# benchBuddy.net
KiCad netlist of a schematic drawn in EAGLE
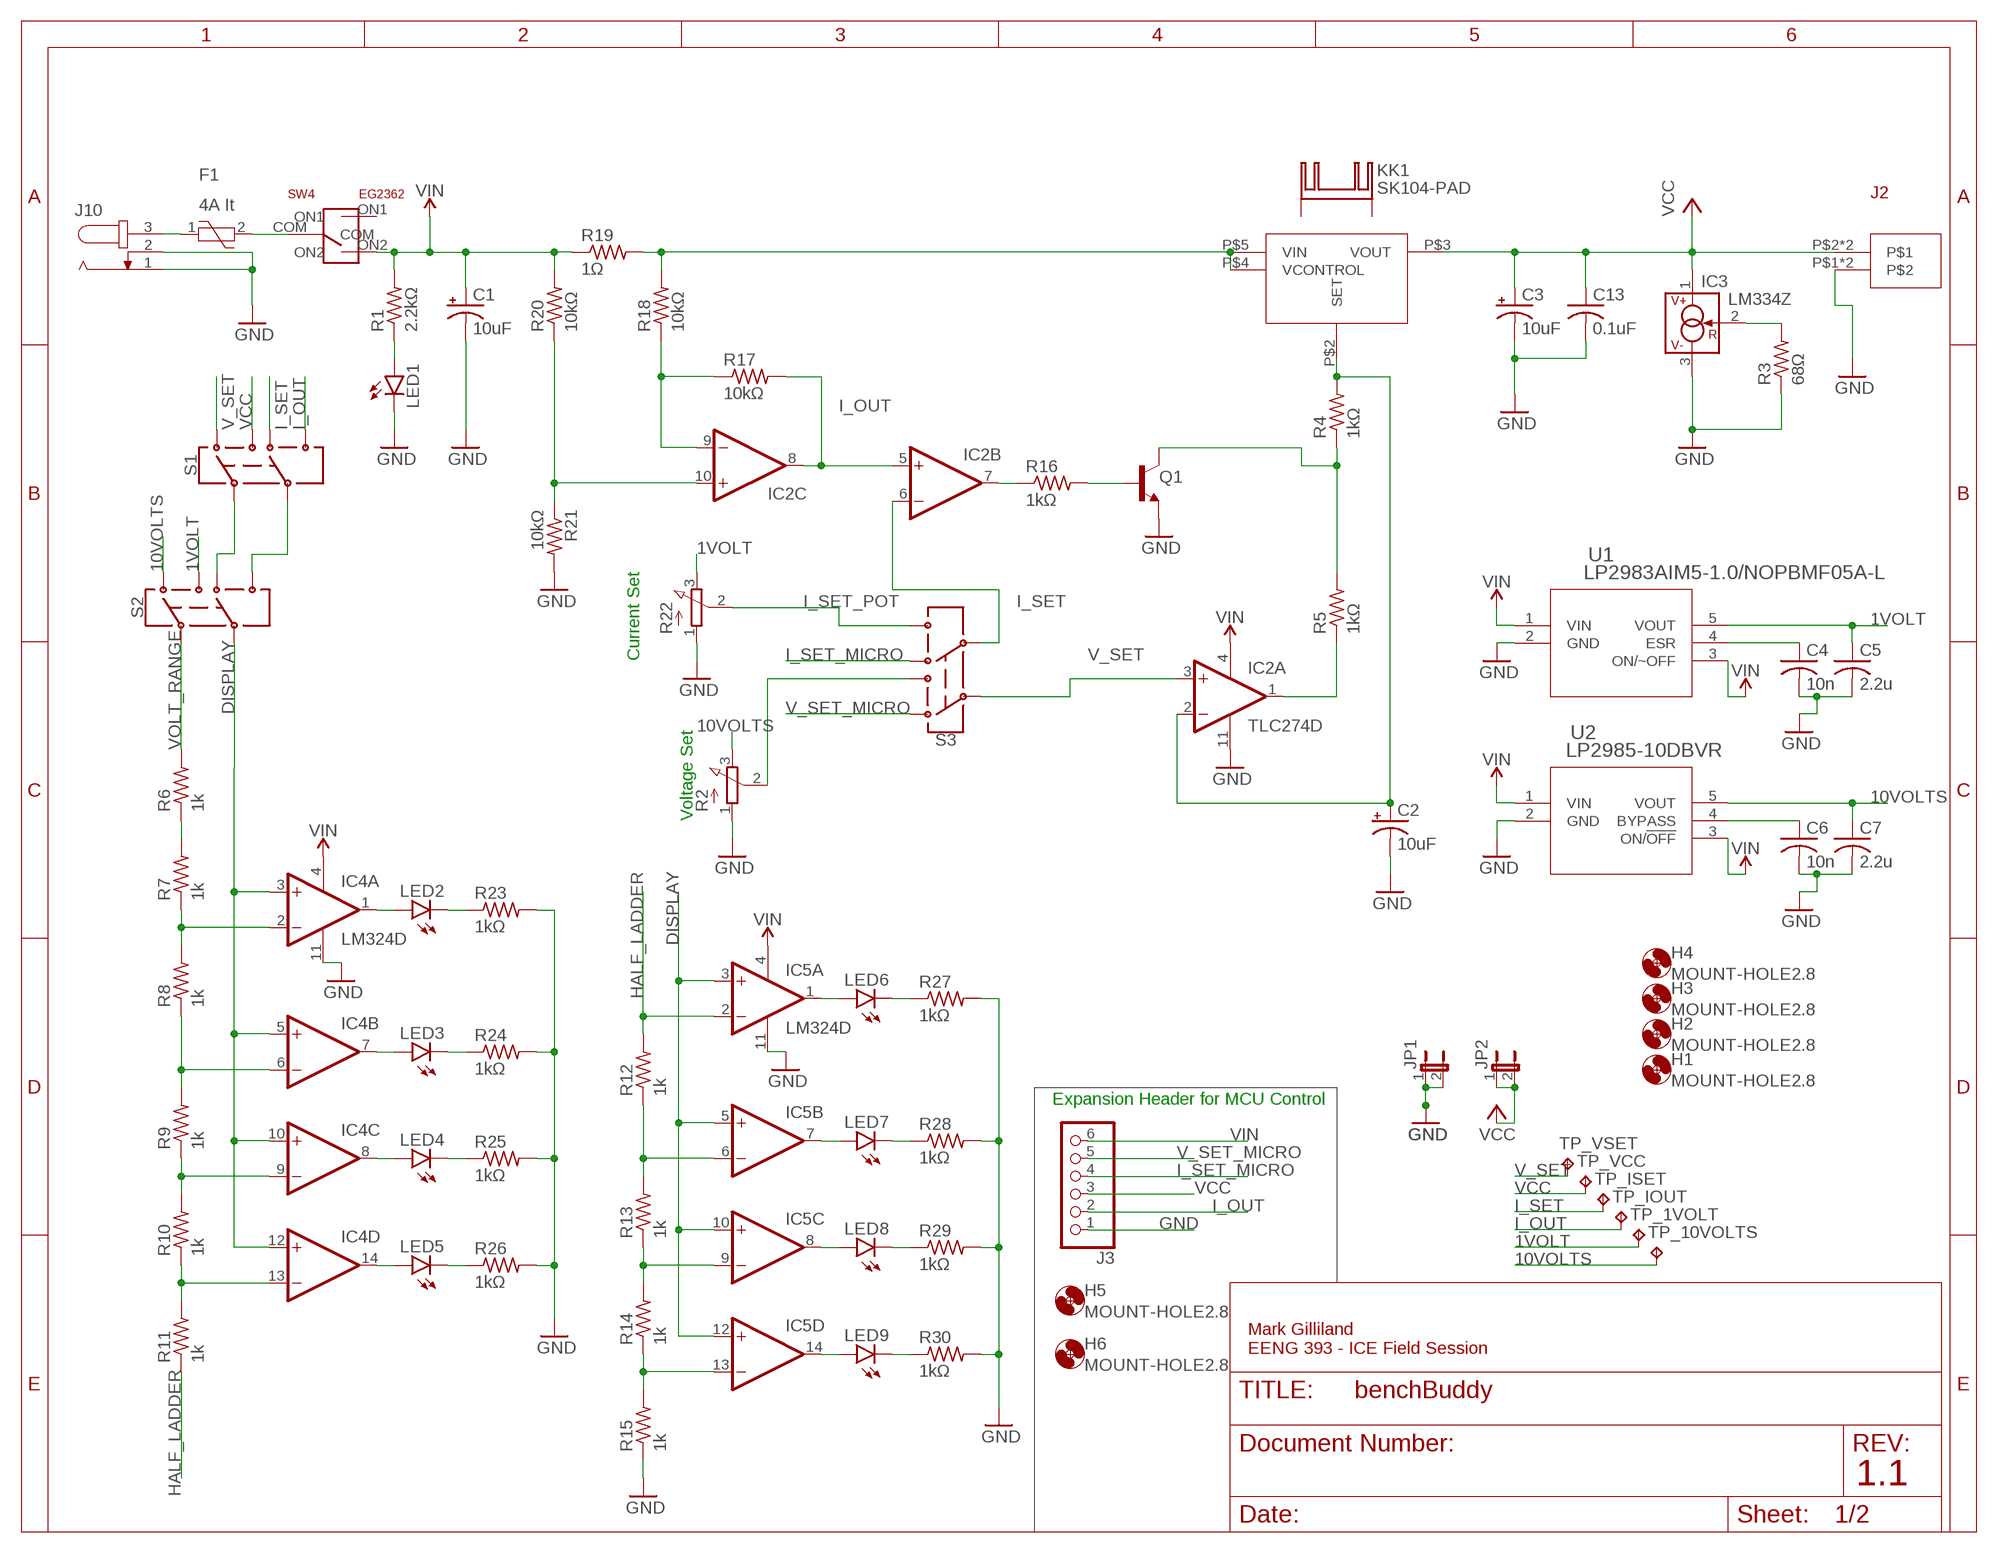
[diagram p0: schematic, sheet 1]
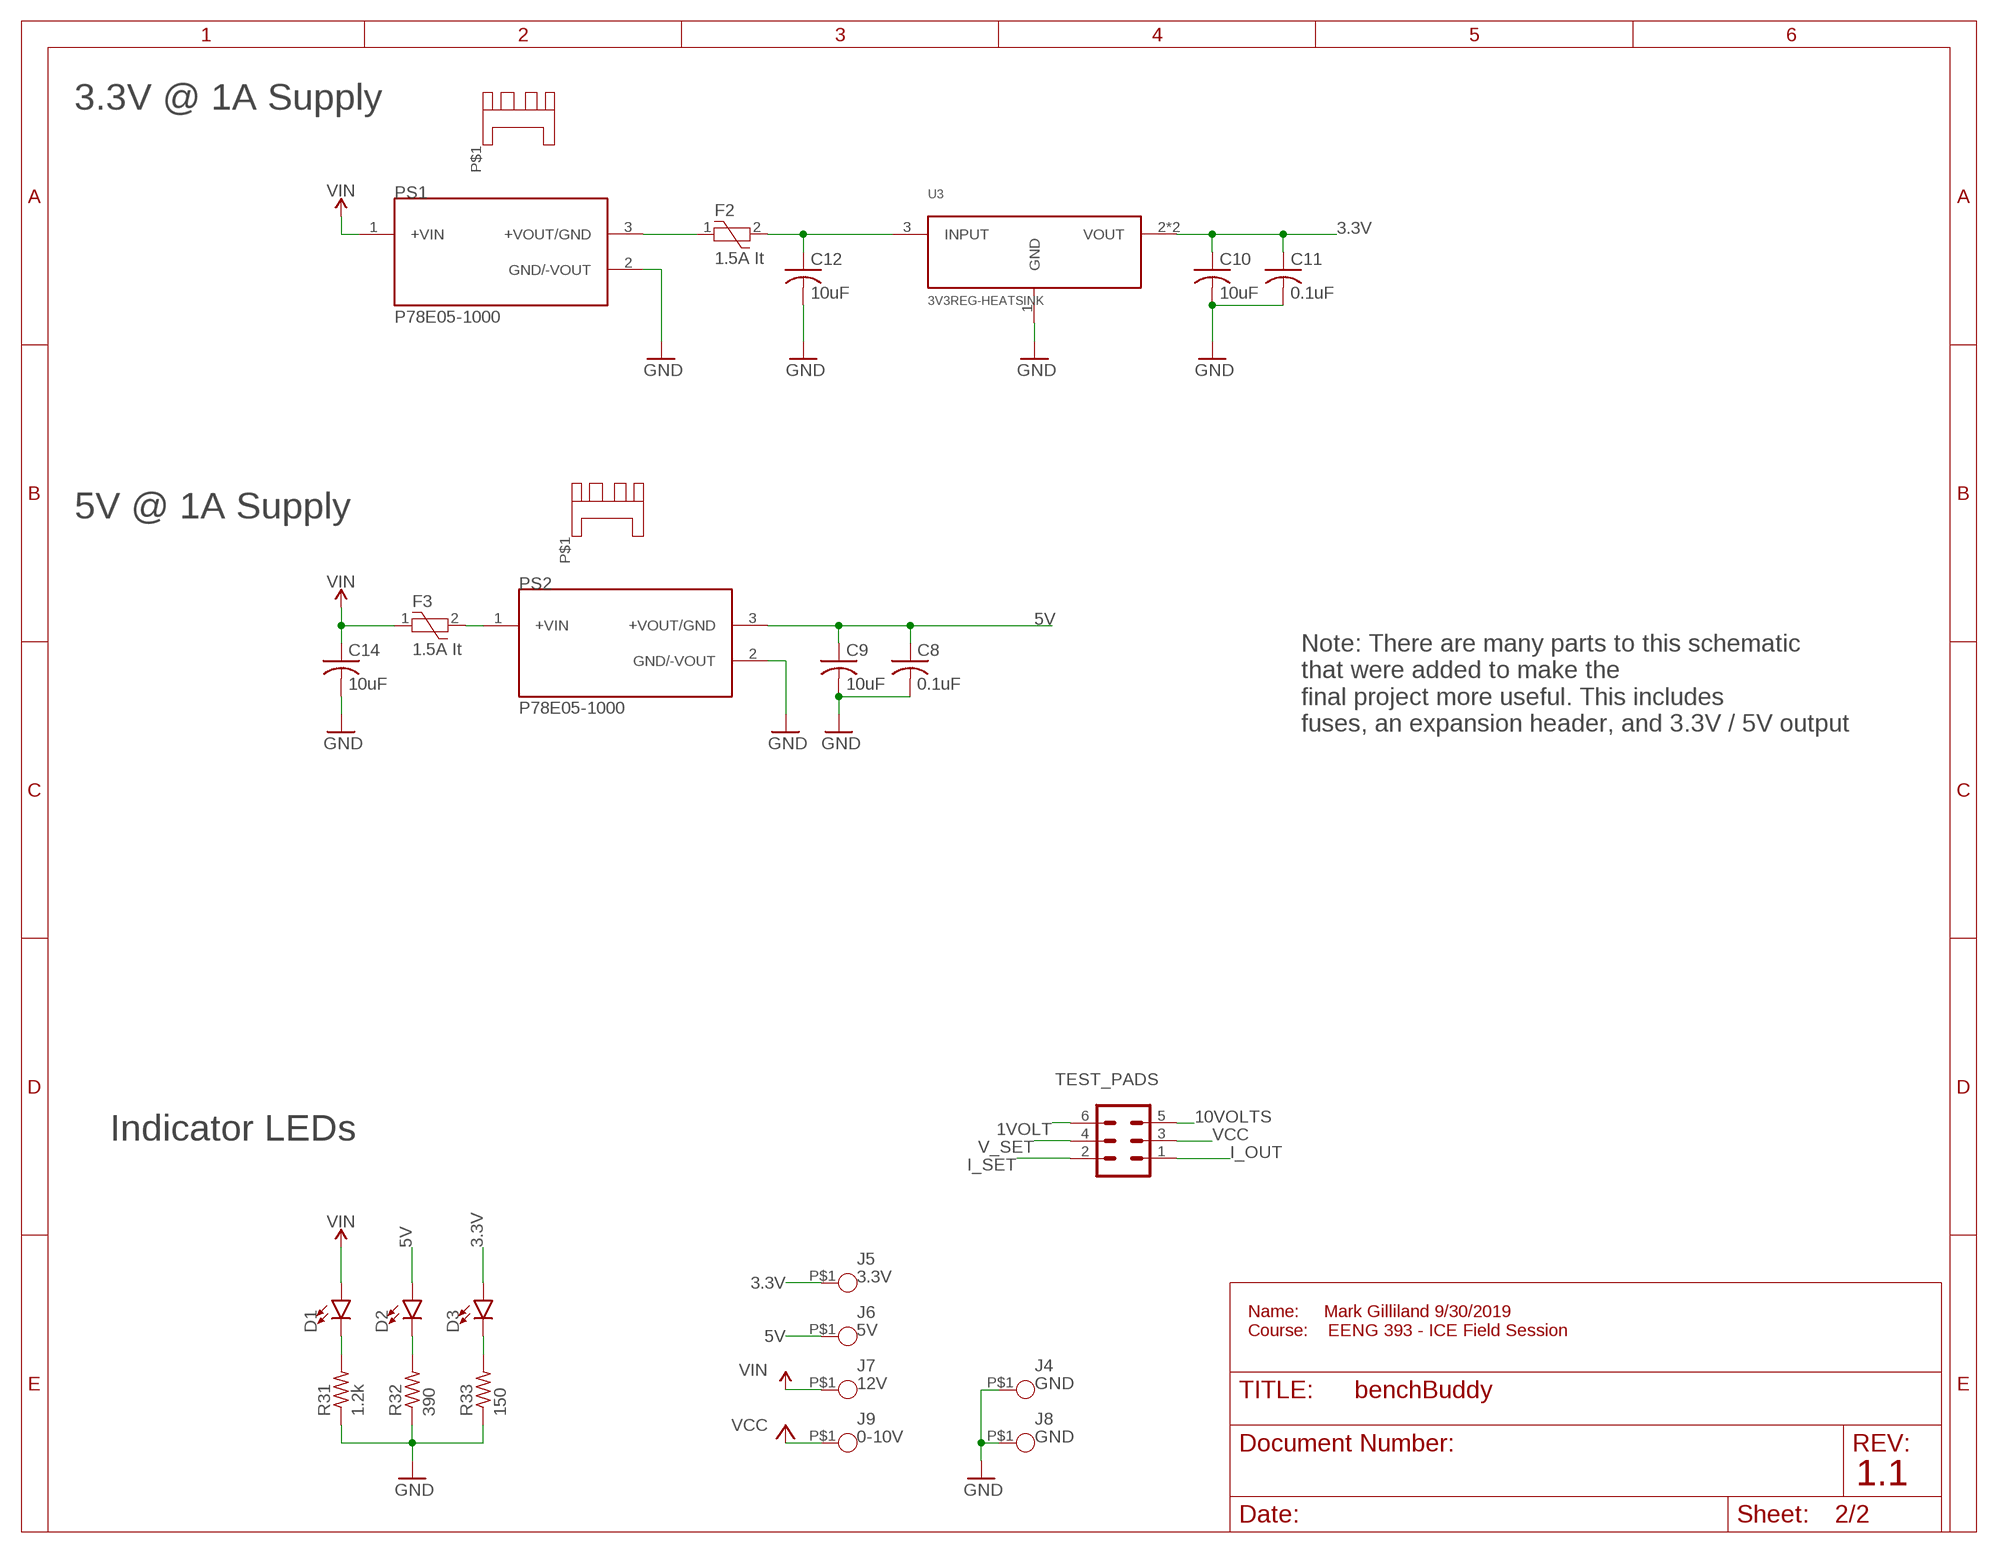
[diagram p1: schematic, sheet 2]

(export (version "E")
  (design (tool "Eeschema 10.0.6"))
  (components
    (comp (ref "C8")
      (value "0.1uF")
      (footprint "eagle-import:C0805")
      (libsource (lib "eagle-import") (part "C-USC0805"))
    )
    (comp (ref "C9")
      (value "10uF")
      (footprint "eagle-import:C0805")
      (libsource (lib "eagle-import") (part "C-USC0805"))
    )
    (comp (ref "C10")
      (value "10uF")
      (footprint "eagle-import:C0805")
      (libsource (lib "eagle-import") (part "C-USC0805"))
    )
    (comp (ref "C11")
      (value "0.1uF")
      (footprint "eagle-import:C0805")
      (libsource (lib "eagle-import") (part "C-USC0805"))
    )
    (comp (ref "C12")
      (value "10uF")
      (footprint "eagle-import:C0805")
      (libsource (lib "eagle-import") (part "C-USC0805"))
    )
    (comp (ref "C14")
      (value "10uF")
      (footprint "eagle-import:C0805")
      (libsource (lib "eagle-import") (part "C-USC0805"))
    )
    (comp (ref "D1")
      (value "LED3MM")
      (footprint "eagle-import:LED_3MM")
      (libsource (lib "eagle-import") (part "LED3MM"))
    )
    (comp (ref "D2")
      (value "LED3MM")
      (footprint "eagle-import:LED_3MM")
      (libsource (lib "eagle-import") (part "LED3MM"))
    )
    (comp (ref "D3")
      (value "LED3MM")
      (footprint "eagle-import:LED_3MM")
      (libsource (lib "eagle-import") (part "LED3MM"))
    )
    (comp (ref "F2")
      (value "1.5A It")
      (footprint "eagle-import:LITTELFUSE_MINISMDC260F_12-2")
      (libsource (lib "eagle-import") (part "FUSE"))
    )
    (comp (ref "F3")
      (value "1.5A It")
      (footprint "eagle-import:LITTELFUSE_MINISMDC260F_12-2")
      (libsource (lib "eagle-import") (part "FUSE"))
    )
    (comp (ref "J4")
      (value "GND")
      (footprint "eagle-import:FAT-PAD")
      (libsource (lib "eagle-import") (part "FAT-WIRE-TERM"))
    )
    (comp (ref "J5")
      (value "3.3V")
      (footprint "eagle-import:FAT-PAD")
      (libsource (lib "eagle-import") (part "FAT-WIRE-TERM"))
    )
    (comp (ref "J6")
      (value "5V")
      (footprint "eagle-import:FAT-PAD")
      (libsource (lib "eagle-import") (part "FAT-WIRE-TERM"))
    )
    (comp (ref "J7")
      (value "12V")
      (footprint "eagle-import:FAT-PAD")
      (libsource (lib "eagle-import") (part "FAT-WIRE-TERM"))
    )
    (comp (ref "J8")
      (value "GND")
      (footprint "eagle-import:FAT-PAD")
      (libsource (lib "eagle-import") (part "FAT-WIRE-TERM"))
    )
    (comp (ref "J9")
      (value "0-10V")
      (footprint "eagle-import:FAT-PAD")
      (libsource (lib "eagle-import") (part "FAT-WIRE-TERM"))
    )
    (comp (ref "PS1")
      (value "P78E05-1000")
      (footprint "eagle-import:CONV_P78E05-1000")
      (fields (field (name "MANUFACTURER") "CUI Inc"))
      (libsource (lib "eagle-import") (part "P78E05-1000"))
    )
    (comp (ref "PS2")
      (value "P78E05-1000")
      (footprint "eagle-import:CONV_P78E05-1000")
      (fields (field (name "MANUFACTURER") "CUI Inc"))
      (libsource (lib "eagle-import") (part "P78E05-1000"))
    )
    (comp (ref "R31")
      (value "1.2k")
      (footprint "eagle-import:R1206")
      (libsource (lib "eagle-import") (part "R-US_R1206"))
    )
    (comp (ref "R32")
      (value "390")
      (footprint "eagle-import:R1206")
      (libsource (lib "eagle-import") (part "R-US_R1206"))
    )
    (comp (ref "R33")
      (value "150")
      (footprint "eagle-import:R1206")
      (libsource (lib "eagle-import") (part "R-US_R1206"))
    )
    (comp (ref "TEST_PADS")
      (value "CONN_03X2NO_SILK")
      (footprint "eagle-import:2X3-NS")
      (libsource (lib "eagle-import") (part "CONN_03X2NO_SILK"))
    )
    (comp (ref "U$2")
      (value "HEATSINK_MINI")
      (footprint "eagle-import:HEATSINK_MINI")
      (libsource (lib "eagle-import") (part "HEATSINK_MINI"))
    )
    (comp (ref "U$3")
      (value "HEATSINK_MINI")
      (footprint "eagle-import:HEATSINK_MINI")
      (libsource (lib "eagle-import") (part "HEATSINK_MINI"))
    )
    (comp (ref "U3")
      (value "3V3REG-HEATSINK")
      (footprint "eagle-import:SOT223-HS")
      (libsource (lib "eagle-import") (part "3V3REG-HEATSINK"))
    )
    (comp (ref "C1")
      (value "10uF")
      (footprint "eagle-import:PANASONIC_B")
      (libsource (lib "eagle-import") (part "CPOL-USB"))
    )
    (comp (ref "C2")
      (value "10uF")
      (footprint "eagle-import:PANASONIC_B")
      (libsource (lib "eagle-import") (part "CPOL-USB"))
    )
    (comp (ref "C3")
      (value "10uF")
      (footprint "eagle-import:PANASONIC_B")
      (libsource (lib "eagle-import") (part "CPOL-USB"))
    )
    (comp (ref "C4")
      (value "10n")
      (footprint "eagle-import:C1206")
      (libsource (lib "eagle-import") (part "C-USC1206"))
    )
    (comp (ref "C5")
      (value "2.2u")
      (footprint "eagle-import:C1206")
      (libsource (lib "eagle-import") (part "C-USC1206"))
    )
    (comp (ref "C6")
      (value "10n")
      (footprint "eagle-import:C1206")
      (libsource (lib "eagle-import") (part "C-USC1206"))
    )
    (comp (ref "C7")
      (value "2.2u")
      (footprint "eagle-import:C1206")
      (libsource (lib "eagle-import") (part "C-USC1206"))
    )
    (comp (ref "C13")
      (value "0.1uF")
      (footprint "eagle-import:C0805")
      (libsource (lib "eagle-import") (part "C-USC0805"))
    )
    (comp (ref "F1")
      (value "4A It")
      (footprint "eagle-import:LITTELFUSE_MINISMDC260F_12-2")
      (libsource (lib "eagle-import") (part "FUSE"))
    )
    (comp (ref "H1")
      (value "MOUNT-HOLE2.8")
      (footprint "eagle-import:2,8")
      (libsource (lib "eagle-import") (part "MOUNT-HOLE2.8"))
    )
    (comp (ref "H2")
      (value "MOUNT-HOLE2.8")
      (footprint "eagle-import:2,8")
      (libsource (lib "eagle-import") (part "MOUNT-HOLE2.8"))
    )
    (comp (ref "H3")
      (value "MOUNT-HOLE2.8")
      (footprint "eagle-import:2,8")
      (libsource (lib "eagle-import") (part "MOUNT-HOLE2.8"))
    )
    (comp (ref "H4")
      (value "MOUNT-HOLE2.8")
      (footprint "eagle-import:2,8")
      (libsource (lib "eagle-import") (part "MOUNT-HOLE2.8"))
    )
    (comp (ref "H5")
      (value "MOUNT-HOLE2.8")
      (footprint "eagle-import:2,8")
      (libsource (lib "eagle-import") (part "MOUNT-HOLE2.8"))
    )
    (comp (ref "H6")
      (value "MOUNT-HOLE2.8")
      (footprint "eagle-import:2,8")
      (libsource (lib "eagle-import") (part "MOUNT-HOLE2.8"))
    )
    (comp (ref "IC2")
      (value "TLC274D")
      (footprint "eagle-import:SO14")
      (libsource (lib "eagle-import") (part "TLC274D"))
    )
    (comp (ref "IC3")
      (value "LM334Z")
      (footprint "eagle-import:TO92")
      (libsource (lib "eagle-import") (part "LM34Z3"))
    )
    (comp (ref "IC4")
      (value "LM324D")
      (footprint "eagle-import:SO14")
      (libsource (lib "eagle-import") (part "LM324D"))
    )
    (comp (ref "IC5")
      (value "LM324D")
      (footprint "eagle-import:SO14")
      (libsource (lib "eagle-import") (part "LM324D"))
    )
    (comp (ref "J2")
      (value "PHOENIX_SPRING_TERM_2POS")
      (footprint "eagle-import:SPRING_TERM_2POS")
      (libsource (lib "eagle-import") (part "PHOENIX_SPRING_TERM_2POS"))
    )
    (comp (ref "J3")
      (value "PINHD-1X6")
      (footprint "eagle-import:1X06")
      (libsource (lib "eagle-import") (part "PINHD-1X6"))
    )
    (comp (ref "J10")
      (value "JACK-PLUG0")
      (footprint "eagle-import:SPC4077")
      (libsource (lib "eagle-import") (part "JACK-PLUG0"))
    )
    (comp (ref "JP1")
      (value "JP1E")
      (footprint "eagle-import:JP1")
      (libsource (lib "eagle-import") (part "JP1E"))
    )
    (comp (ref "JP2")
      (value "JP1E")
      (footprint "eagle-import:JP1")
      (libsource (lib "eagle-import") (part "JP1E"))
    )
    (comp (ref "KK1")
      (value "SK104-PAD")
      (footprint "eagle-import:SK104-PAD")
      (libsource (lib "eagle-import") (part "SK104-PAD"))
    )
    (comp (ref "LED1")
      (value "LEDCHIPLED_1206")
      (footprint "eagle-import:CHIPLED_1206")
      (libsource (lib "eagle-import") (part "LEDCHIPLED_1206"))
    )
    (comp (ref "LED2")
      (value "LEDCHIPLED_1206")
      (footprint "eagle-import:CHIPLED_1206")
      (libsource (lib "eagle-import") (part "LEDCHIPLED_1206"))
    )
    (comp (ref "LED3")
      (value "LEDCHIPLED_1206")
      (footprint "eagle-import:CHIPLED_1206")
      (libsource (lib "eagle-import") (part "LEDCHIPLED_1206"))
    )
    (comp (ref "LED4")
      (value "LEDCHIPLED_1206")
      (footprint "eagle-import:CHIPLED_1206")
      (libsource (lib "eagle-import") (part "LEDCHIPLED_1206"))
    )
    (comp (ref "LED5")
      (value "LEDCHIPLED_1206")
      (footprint "eagle-import:CHIPLED_1206")
      (libsource (lib "eagle-import") (part "LEDCHIPLED_1206"))
    )
    (comp (ref "LED6")
      (value "LEDCHIPLED_1206")
      (footprint "eagle-import:CHIPLED_1206")
      (libsource (lib "eagle-import") (part "LEDCHIPLED_1206"))
    )
    (comp (ref "LED7")
      (value "LEDCHIPLED_1206")
      (footprint "eagle-import:CHIPLED_1206")
      (libsource (lib "eagle-import") (part "LEDCHIPLED_1206"))
    )
    (comp (ref "LED8")
      (value "LEDCHIPLED_1206")
      (footprint "eagle-import:CHIPLED_1206")
      (libsource (lib "eagle-import") (part "LEDCHIPLED_1206"))
    )
    (comp (ref "LED9")
      (value "LEDCHIPLED_1206")
      (footprint "eagle-import:CHIPLED_1206")
      (libsource (lib "eagle-import") (part "LEDCHIPLED_1206"))
    )
    (comp (ref "Q1")
      (value "600mA/40V")
      (footprint "eagle-import:SOT23-3")
      (libsource (lib "eagle-import") (part "TRANS_NPN-MMBT2222AL"))
    )
    (comp (ref "R1")
      (value "2.2kΩ")
      (footprint "eagle-import:R1206")
      (libsource (lib "eagle-import") (part "R-US_R1206"))
    )
    (comp (ref "R2")
      (value "EVUF2A")
      (footprint "eagle-import:EVUF")
      (libsource (lib "eagle-import") (part "EVUAF2"))
    )
    (comp (ref "R3")
      (value "68Ω")
      (footprint "eagle-import:R1206")
      (libsource (lib "eagle-import") (part "R-US_R1206"))
    )
    (comp (ref "R4")
      (value "1kΩ")
      (footprint "eagle-import:R1206")
      (libsource (lib "eagle-import") (part "R-US_R1206"))
    )
    (comp (ref "R5")
      (value "1kΩ")
      (footprint "eagle-import:R1206")
      (libsource (lib "eagle-import") (part "R-US_R1206"))
    )
    (comp (ref "R6")
      (value "1k")
      (footprint "eagle-import:R1206")
      (libsource (lib "eagle-import") (part "R-US_R1206"))
    )
    (comp (ref "R7")
      (value "1k")
      (footprint "eagle-import:R1206")
      (libsource (lib "eagle-import") (part "R-US_R1206"))
    )
    (comp (ref "R8")
      (value "1k")
      (footprint "eagle-import:R1206")
      (libsource (lib "eagle-import") (part "R-US_R1206"))
    )
    (comp (ref "R9")
      (value "1k")
      (footprint "eagle-import:R1206")
      (libsource (lib "eagle-import") (part "R-US_R1206"))
    )
    (comp (ref "R10")
      (value "1k")
      (footprint "eagle-import:R1206")
      (libsource (lib "eagle-import") (part "R-US_R1206"))
    )
    (comp (ref "R11")
      (value "1k")
      (footprint "eagle-import:R1206")
      (libsource (lib "eagle-import") (part "R-US_R1206"))
    )
    (comp (ref "R12")
      (value "1k")
      (footprint "eagle-import:R1206")
      (libsource (lib "eagle-import") (part "R-US_R1206"))
    )
    (comp (ref "R13")
      (value "1k")
      (footprint "eagle-import:R1206")
      (libsource (lib "eagle-import") (part "R-US_R1206"))
    )
    (comp (ref "R14")
      (value "1k")
      (footprint "eagle-import:R1206")
      (libsource (lib "eagle-import") (part "R-US_R1206"))
    )
    (comp (ref "R15")
      (value "1k")
      (footprint "eagle-import:R1206")
      (libsource (lib "eagle-import") (part "R-US_R1206"))
    )
    (comp (ref "R16")
      (value "1kΩ")
      (footprint "eagle-import:R1206")
      (libsource (lib "eagle-import") (part "R-US_R1206"))
    )
    (comp (ref "R17")
      (value "10kΩ")
      (footprint "eagle-import:R1206")
      (libsource (lib "eagle-import") (part "R-US_R1206"))
    )
    (comp (ref "R18")
      (value "10kΩ")
      (footprint "eagle-import:R1206")
      (libsource (lib "eagle-import") (part "R-US_R1206"))
    )
    (comp (ref "R19")
      (value "1Ω")
      (footprint "eagle-import:0411_15")
      (libsource (lib "eagle-import") (part "R-US_0411/15"))
    )
    (comp (ref "R20")
      (value "10kΩ")
      (footprint "eagle-import:R1206")
      (libsource (lib "eagle-import") (part "R-US_R1206"))
    )
    (comp (ref "R21")
      (value "10kΩ")
      (footprint "eagle-import:R1206")
      (libsource (lib "eagle-import") (part "R-US_R1206"))
    )
    (comp (ref "R22")
      (value "EVUF2A")
      (footprint "eagle-import:EVUF")
      (libsource (lib "eagle-import") (part "EVUAF2"))
    )
    (comp (ref "R23")
      (value "1kΩ")
      (footprint "eagle-import:R1206")
      (libsource (lib "eagle-import") (part "R-US_R1206"))
    )
    (comp (ref "R24")
      (value "1kΩ")
      (footprint "eagle-import:R1206")
      (libsource (lib "eagle-import") (part "R-US_R1206"))
    )
    (comp (ref "R25")
      (value "1kΩ")
      (footprint "eagle-import:R1206")
      (libsource (lib "eagle-import") (part "R-US_R1206"))
    )
    (comp (ref "R26")
      (value "1kΩ")
      (footprint "eagle-import:R1206")
      (libsource (lib "eagle-import") (part "R-US_R1206"))
    )
    (comp (ref "R27")
      (value "1kΩ")
      (footprint "eagle-import:R1206")
      (libsource (lib "eagle-import") (part "R-US_R1206"))
    )
    (comp (ref "R28")
      (value "1kΩ")
      (footprint "eagle-import:R1206")
      (libsource (lib "eagle-import") (part "R-US_R1206"))
    )
    (comp (ref "R29")
      (value "1kΩ")
      (footprint "eagle-import:R1206")
      (libsource (lib "eagle-import") (part "R-US_R1206"))
    )
    (comp (ref "R30")
      (value "1kΩ")
      (footprint "eagle-import:R1206")
      (libsource (lib "eagle-import") (part "R-US_R1206"))
    )
    (comp (ref "S1")
      (value "SWITCH-DPDT-SMD-AYZ0202")
      (footprint "eagle-import:SWITCH_DPDT_SMD_AYZ0202")
      (libsource (lib "eagle-import") (part "SWITCH-DPDT-SMD-AYZ0202"))
    )
    (comp (ref "S2")
      (value "SWITCH-DPDT-SMD-AYZ0202")
      (footprint "eagle-import:SWITCH_DPDT_SMD_AYZ0202")
      (libsource (lib "eagle-import") (part "SWITCH-DPDT-SMD-AYZ0202"))
    )
    (comp (ref "S3")
      (value "SWITCH-DPDT-SMD-AYZ0202")
      (footprint "eagle-import:SWITCH_DPDT_SMD_AYZ0202")
      (libsource (lib "eagle-import") (part "SWITCH-DPDT-SMD-AYZ0202"))
    )
    (comp (ref "SW4")
      (value "EG2362")
      (footprint "eagle-import:SWITCH_EG2362-ND")
      (libsource (lib "eagle-import") (part "EG2362"))
    )
    (comp (ref "TP_1VOLT")
      (value "TPB1,27")
      (footprint "eagle-import:B1,27")
      (libsource (lib "eagle-import") (part "TPB1,27"))
    )
    (comp (ref "TP_10VOLTS")
      (value "TPB1,27")
      (footprint "eagle-import:B1,27")
      (libsource (lib "eagle-import") (part "TPB1,27"))
    )
    (comp (ref "TP_IOUT")
      (value "TPB1,27")
      (footprint "eagle-import:B1,27")
      (libsource (lib "eagle-import") (part "TPB1,27"))
    )
    (comp (ref "TP_ISET")
      (value "TPB1,27")
      (footprint "eagle-import:B1,27")
      (libsource (lib "eagle-import") (part "TPB1,27"))
    )
    (comp (ref "TP_VCC")
      (value "TPB1,27")
      (footprint "eagle-import:B1,27")
      (libsource (lib "eagle-import") (part "TPB1,27"))
    )
    (comp (ref "TP_VSET")
      (value "TPB1,27")
      (footprint "eagle-import:B1,27")
      (libsource (lib "eagle-import") (part "TPB1,27"))
    )
    (comp (ref "U$1")
      (value "LT3080")
      (footprint "eagle-import:TO-220-5R")
      (libsource (lib "eagle-import") (part "LT3080"))
    )
    (comp (ref "U1")
      (value "LP2983AIM5-1.0/NOPBMF05A-L")
      (footprint "eagle-import:MF05A-L")
      (fields (field (name "MANUFACTURER_PART_NUMBER") "LP2983AIM51.0NOPB"))
      (libsource (lib "eagle-import") (part "LP2983AIM5-1.0/NOPBMF05A-L"))
    )
    (comp (ref "U2")
      (value "LP2985-10DBVR")
      (footprint "eagle-import:DBV5")
      (fields (field (name "MANUFACTURER_PART_NUMBER") "LP298510DBVR"))
      (libsource (lib "eagle-import") (part "LP2985-10DBVR"))
    )
  )
  (nets
    (net (code "1") (name "1VOLT") (class "Default")
      (node (ref "C5") (pin "1") (pinfunction "1_1") (pintype "passive"))
      (node (ref "R22") (pin "3") (pinfunction "E_3") (pintype "passive"))
      (node (ref "S2") (pin "3") (pinfunction "3_3") (pintype "bidirectional"))
      (node (ref "TEST_PADS") (pin "6") (pinfunction "6_6") (pintype "bidirectional"))
      (node (ref "TP_1VOLT") (pin "TP") (pinfunction "TP_TP") (pintype "input"))
      (node (ref "U1") (pin "5") (pinfunction "VOUT_5") (pintype "output"))
    )
    (net (code "2") (name "3.3V") (class "Default")
      (node (ref "C10") (pin "1") (pinfunction "1_1") (pintype "passive"))
      (node (ref "C11") (pin "1") (pinfunction "1_1") (pintype "passive"))
      (node (ref "D3") (pin "A") (pinfunction "A_A") (pintype "passive"))
      (node (ref "J5") (pin "P$1") (pinfunction "P$1_P$1") (pintype "bidirectional"))
      (node (ref "U3") (pin "2") (pinfunction "VOUT_2") (pintype "bidirectional"))
      (node (ref "U3") (pin "4") (pinfunction "VOUT_4") (pintype "bidirectional"))
    )
    (net (code "3") (name "5V") (class "Default")
      (node (ref "C8") (pin "1") (pinfunction "1_1") (pintype "passive"))
      (node (ref "C9") (pin "1") (pinfunction "1_1") (pintype "passive"))
      (node (ref "D2") (pin "A") (pinfunction "A_A") (pintype "passive"))
      (node (ref "J6") (pin "P$1") (pinfunction "P$1_P$1") (pintype "bidirectional"))
      (node (ref "PS2") (pin "3") (pinfunction "+VOUT/GND_3") (pintype "power_in"))
    )
    (net (code "4") (name "10VOLTS") (class "Default")
      (node (ref "C7") (pin "1") (pinfunction "1_1") (pintype "passive"))
      (node (ref "R2") (pin "3") (pinfunction "E_3") (pintype "passive"))
      (node (ref "S2") (pin "1") (pinfunction "1_1") (pintype "bidirectional"))
      (node (ref "TEST_PADS") (pin "5") (pinfunction "5_5") (pintype "bidirectional"))
      (node (ref "TP_10VOLTS") (pin "TP") (pinfunction "TP_TP") (pintype "input"))
      (node (ref "U2") (pin "5") (pinfunction "VOUT_5") (pintype "output"))
    )
    (net (code "5") (name "DISPLAY") (class "Default")
      (node (ref "IC4") (pin "10") (pinfunction "+IN_10") (pintype "input"))
      (node (ref "IC4") (pin "12") (pinfunction "+IN_12") (pintype "input"))
      (node (ref "IC4") (pin "3") (pinfunction "+IN_3") (pintype "input"))
      (node (ref "IC4") (pin "5") (pinfunction "+IN_5") (pintype "input"))
      (node (ref "IC5") (pin "10") (pinfunction "+IN_10") (pintype "input"))
      (node (ref "IC5") (pin "12") (pinfunction "+IN_12") (pintype "input"))
      (node (ref "IC5") (pin "3") (pinfunction "+IN_3") (pintype "input"))
      (node (ref "IC5") (pin "5") (pinfunction "+IN_5") (pintype "input"))
      (node (ref "S2") (pin "5") (pinfunction "5_5") (pintype "bidirectional"))
    )
    (net (code "6") (name "GND") (class "Default")
      (node (ref "C1") (pin "-") (pinfunction "-_-") (pintype "passive"))
      (node (ref "C10") (pin "2") (pinfunction "2_2") (pintype "passive"))
      (node (ref "C11") (pin "2") (pinfunction "2_2") (pintype "passive"))
      (node (ref "C12") (pin "2") (pinfunction "2_2") (pintype "passive"))
      (node (ref "C13") (pin "2") (pinfunction "2_2") (pintype "passive"))
      (node (ref "C14") (pin "2") (pinfunction "2_2") (pintype "passive"))
      (node (ref "C2") (pin "-") (pinfunction "-_-") (pintype "passive"))
      (node (ref "C3") (pin "-") (pinfunction "-_-") (pintype "passive"))
      (node (ref "C4") (pin "2") (pinfunction "2_2") (pintype "passive"))
      (node (ref "C5") (pin "2") (pinfunction "2_2") (pintype "passive"))
      (node (ref "C6") (pin "2") (pinfunction "2_2") (pintype "passive"))
      (node (ref "C7") (pin "2") (pinfunction "2_2") (pintype "passive"))
      (node (ref "C8") (pin "2") (pinfunction "2_2") (pintype "passive"))
      (node (ref "C9") (pin "2") (pinfunction "2_2") (pintype "passive"))
      (node (ref "IC2") (pin "11") (pinfunction "V-_11") (pintype "power_in"))
      (node (ref "IC3") (pin "3") (pinfunction "V-_3") (pintype "passive"))
      (node (ref "IC4") (pin "11") (pinfunction "V-_11") (pintype "power_in"))
      (node (ref "IC5") (pin "11") (pinfunction "V-_11") (pintype "power_in"))
      (node (ref "J10") (pin "1") (pinfunction "1_1") (pintype "passive"))
      (node (ref "J10") (pin "2") (pinfunction "2_2") (pintype "passive"))
      (node (ref "J2") (pin "P$1") (pinfunction "P$2_P$1") (pintype "bidirectional"))
      (node (ref "J2") (pin "P$3") (pinfunction "P$2_P$3") (pintype "bidirectional"))
      (node (ref "J3") (pin "1") (pinfunction "1_1") (pintype "passive"))
      (node (ref "J4") (pin "P$1") (pinfunction "P$1_P$1") (pintype "bidirectional"))
      (node (ref "J8") (pin "P$1") (pinfunction "P$1_P$1") (pintype "bidirectional"))
      (node (ref "JP1") (pin "1") (pinfunction "1_1") (pintype "passive"))
      (node (ref "JP1") (pin "2") (pinfunction "2_2") (pintype "passive"))
      (node (ref "LED1") (pin "C") (pinfunction "C_C") (pintype "passive"))
      (node (ref "PS1") (pin "2") (pinfunction "GND/-VOUT_2") (pintype "power_in"))
      (node (ref "PS2") (pin "2") (pinfunction "GND/-VOUT_2") (pintype "power_in"))
      (node (ref "Q1") (pin "2") (pinfunction "E_2") (pintype "passive"))
      (node (ref "R15") (pin "1") (pinfunction "1_1") (pintype "passive"))
      (node (ref "R2") (pin "1") (pinfunction "A_1") (pintype "passive"))
      (node (ref "R21") (pin "2") (pinfunction "2_2") (pintype "passive"))
      (node (ref "R22") (pin "1") (pinfunction "A_1") (pintype "passive"))
      (node (ref "R23") (pin "2") (pinfunction "2_2") (pintype "passive"))
      (node (ref "R24") (pin "2") (pinfunction "2_2") (pintype "passive"))
      (node (ref "R25") (pin "2") (pinfunction "2_2") (pintype "passive"))
      (node (ref "R26") (pin "2") (pinfunction "2_2") (pintype "passive"))
      (node (ref "R27") (pin "2") (pinfunction "2_2") (pintype "passive"))
      (node (ref "R28") (pin "2") (pinfunction "2_2") (pintype "passive"))
      (node (ref "R29") (pin "2") (pinfunction "2_2") (pintype "passive"))
      (node (ref "R3") (pin "1") (pinfunction "1_1") (pintype "passive"))
      (node (ref "R30") (pin "2") (pinfunction "2_2") (pintype "passive"))
      (node (ref "R31") (pin "1") (pinfunction "1_1") (pintype "passive"))
      (node (ref "R32") (pin "1") (pinfunction "1_1") (pintype "passive"))
      (node (ref "R33") (pin "1") (pinfunction "1_1") (pintype "passive"))
      (node (ref "U1") (pin "2") (pinfunction "GND_2") (pintype "passive"))
      (node (ref "U2") (pin "2") (pinfunction "GND_2") (pintype "power_in"))
      (node (ref "U3") (pin "1") (pinfunction "GND_1") (pintype "bidirectional"))
    )
    (net (code "7") (name "HALF_LADDER") (class "Default")
      (node (ref "IC5") (pin "2") (pinfunction "-IN_2") (pintype "input"))
      (node (ref "R11") (pin "1") (pinfunction "1_1") (pintype "passive"))
      (node (ref "R12") (pin "2") (pinfunction "2_2") (pintype "passive"))
    )
    (net (code "8") (name "I_OUT") (class "Default")
      (node (ref "IC2") (pin "5") (pinfunction "+IN_5") (pintype "input"))
      (node (ref "IC2") (pin "8") (pinfunction "OUT_8") (pintype "output"))
      (node (ref "J3") (pin "2") (pinfunction "2_2") (pintype "passive"))
      (node (ref "R17") (pin "2") (pinfunction "2_2") (pintype "passive"))
      (node (ref "S1") (pin "6") (pinfunction "6_6") (pintype "bidirectional"))
      (node (ref "TEST_PADS") (pin "1") (pinfunction "1_1") (pintype "bidirectional"))
      (node (ref "TP_IOUT") (pin "TP") (pinfunction "TP_TP") (pintype "input"))
    )
    (net (code "9") (name "I_SET") (class "Default")
      (node (ref "IC2") (pin "6") (pinfunction "-IN_6") (pintype "input"))
      (node (ref "S1") (pin "4") (pinfunction "4_4") (pintype "bidirectional"))
      (node (ref "S3") (pin "5") (pinfunction "5_5") (pintype "bidirectional"))
      (node (ref "TEST_PADS") (pin "2") (pinfunction "2_2") (pintype "bidirectional"))
      (node (ref "TP_ISET") (pin "TP") (pinfunction "TP_TP") (pintype "input"))
    )
    (net (code "10") (name "I_SET_MICRO") (class "Default")
      (node (ref "J3") (pin "4") (pinfunction "4_4") (pintype "passive"))
      (node (ref "S3") (pin "4") (pinfunction "4_4") (pintype "bidirectional"))
    )
    (net (code "11") (name "I_SET_POT") (class "Default")
      (node (ref "R22") (pin "2") (pinfunction "S_2") (pintype "passive"))
      (node (ref "S3") (pin "6") (pinfunction "6_6") (pintype "bidirectional"))
    )
    (net (code "12") (name "Net-(D1-C)") (class "Default")
      (node (ref "D1") (pin "K") (pinfunction "C_K") (pintype "passive"))
      (node (ref "R31") (pin "2") (pinfunction "2_2") (pintype "passive"))
    )
    (net (code "13") (name "Net-(D2-C)") (class "Default")
      (node (ref "D2") (pin "K") (pinfunction "C_K") (pintype "passive"))
      (node (ref "R32") (pin "2") (pinfunction "2_2") (pintype "passive"))
    )
    (net (code "14") (name "Net-(D3-C)") (class "Default")
      (node (ref "D3") (pin "K") (pinfunction "C_K") (pintype "passive"))
      (node (ref "R33") (pin "2") (pinfunction "2_2") (pintype "passive"))
    )
    (net (code "15") (name "Net-(F1-P$1)") (class "Default")
      (node (ref "F1") (pin "1") (pinfunction "P$1_1") (pintype "bidirectional"))
      (node (ref "J10") (pin "3") (pinfunction "3_3") (pintype "passive"))
    )
    (net (code "16") (name "Net-(F1-P$2)") (class "Default")
      (node (ref "F1") (pin "2") (pinfunction "P$2_2") (pintype "bidirectional"))
      (node (ref "SW4") (pin "COM") (pinfunction "COM_COM") (pintype "power_in"))
    )
    (net (code "17") (name "Net-(F2-P$1)") (class "Default")
      (node (ref "F2") (pin "1") (pinfunction "P$1_1") (pintype "bidirectional"))
      (node (ref "PS1") (pin "3") (pinfunction "+VOUT/GND_3") (pintype "power_in"))
    )
    (net (code "18") (name "Net-(F2-P$2)") (class "Default")
      (node (ref "C12") (pin "1") (pinfunction "1_1") (pintype "passive"))
      (node (ref "F2") (pin "2") (pinfunction "P$2_2") (pintype "bidirectional"))
      (node (ref "U3") (pin "3") (pinfunction "INPUT_3") (pintype "bidirectional"))
    )
    (net (code "19") (name "Net-(F3-P$2)") (class "Default")
      (node (ref "F3") (pin "2") (pinfunction "P$2_2") (pintype "bidirectional"))
      (node (ref "PS2") (pin "1") (pinfunction "+VIN_1") (pintype "input"))
    )
    (net (code "20") (name "Net-(IC2A--IN)") (class "Default")
      (node (ref "C2") (pin "+") (pinfunction "+_+") (pintype "passive"))
      (node (ref "IC2") (pin "2") (pinfunction "-IN_2") (pintype "input"))
      (node (ref "R4") (pin "2") (pinfunction "2_2") (pintype "passive"))
      (node (ref "U$1") (pin "P$2") (pinfunction "SET_P$2") (pintype "bidirectional"))
    )
    (net (code "21") (name "Net-(IC2A-OUT)") (class "Default")
      (node (ref "IC2") (pin "1") (pinfunction "OUT_1") (pintype "output"))
      (node (ref "R5") (pin "1") (pinfunction "1_1") (pintype "passive"))
    )
    (net (code "22") (name "Net-(IC2B-OUT)") (class "Default")
      (node (ref "IC2") (pin "7") (pinfunction "OUT_7") (pintype "output"))
      (node (ref "R16") (pin "1") (pinfunction "1_1") (pintype "passive"))
    )
    (net (code "23") (name "Net-(IC2C-+IN)") (class "Default")
      (node (ref "IC2") (pin "10") (pinfunction "+IN_10") (pintype "input"))
      (node (ref "R20") (pin "1") (pinfunction "1_1") (pintype "passive"))
      (node (ref "R21") (pin "1") (pinfunction "1_1") (pintype "passive"))
    )
    (net (code "24") (name "Net-(IC2C--IN)") (class "Default")
      (node (ref "IC2") (pin "9") (pinfunction "-IN_9") (pintype "input"))
      (node (ref "R17") (pin "1") (pinfunction "1_1") (pintype "passive"))
      (node (ref "R18") (pin "1") (pinfunction "1_1") (pintype "passive"))
    )
    (net (code "25") (name "Net-(IC3-R)") (class "Default")
      (node (ref "IC3") (pin "2") (pinfunction "R_2") (pintype "passive"))
      (node (ref "R3") (pin "2") (pinfunction "2_2") (pintype "passive"))
    )
    (net (code "26") (name "Net-(IC4A--IN)") (class "Default")
      (node (ref "IC4") (pin "2") (pinfunction "-IN_2") (pintype "input"))
      (node (ref "R7") (pin "1") (pinfunction "1_1") (pintype "passive"))
      (node (ref "R8") (pin "2") (pinfunction "2_2") (pintype "passive"))
    )
    (net (code "27") (name "Net-(IC4A-OUT)") (class "Default")
      (node (ref "IC4") (pin "1") (pinfunction "OUT_1") (pintype "output"))
      (node (ref "LED2") (pin "A") (pinfunction "A_A") (pintype "passive"))
    )
    (net (code "28") (name "Net-(IC4B--IN)") (class "Default")
      (node (ref "IC4") (pin "6") (pinfunction "-IN_6") (pintype "input"))
      (node (ref "R8") (pin "1") (pinfunction "1_1") (pintype "passive"))
      (node (ref "R9") (pin "2") (pinfunction "2_2") (pintype "passive"))
    )
    (net (code "29") (name "Net-(IC4B-OUT)") (class "Default")
      (node (ref "IC4") (pin "7") (pinfunction "OUT_7") (pintype "output"))
      (node (ref "LED3") (pin "A") (pinfunction "A_A") (pintype "passive"))
    )
    (net (code "30") (name "Net-(IC4C--IN)") (class "Default")
      (node (ref "IC4") (pin "9") (pinfunction "-IN_9") (pintype "input"))
      (node (ref "R10") (pin "2") (pinfunction "2_2") (pintype "passive"))
      (node (ref "R9") (pin "1") (pinfunction "1_1") (pintype "passive"))
    )
    (net (code "31") (name "Net-(IC4C-OUT)") (class "Default")
      (node (ref "IC4") (pin "8") (pinfunction "OUT_8") (pintype "output"))
      (node (ref "LED4") (pin "A") (pinfunction "A_A") (pintype "passive"))
    )
    (net (code "32") (name "Net-(IC4D--IN)") (class "Default")
      (node (ref "IC4") (pin "13") (pinfunction "-IN_13") (pintype "input"))
      (node (ref "R10") (pin "1") (pinfunction "1_1") (pintype "passive"))
      (node (ref "R11") (pin "2") (pinfunction "2_2") (pintype "passive"))
    )
    (net (code "33") (name "Net-(IC4D-OUT)") (class "Default")
      (node (ref "IC4") (pin "14") (pinfunction "OUT_14") (pintype "output"))
      (node (ref "LED5") (pin "A") (pinfunction "A_A") (pintype "passive"))
    )
    (net (code "34") (name "Net-(IC5A-OUT)") (class "Default")
      (node (ref "IC5") (pin "1") (pinfunction "OUT_1") (pintype "output"))
      (node (ref "LED6") (pin "A") (pinfunction "A_A") (pintype "passive"))
    )
    (net (code "35") (name "Net-(IC5B--IN)") (class "Default")
      (node (ref "IC5") (pin "6") (pinfunction "-IN_6") (pintype "input"))
      (node (ref "R12") (pin "1") (pinfunction "1_1") (pintype "passive"))
      (node (ref "R13") (pin "2") (pinfunction "2_2") (pintype "passive"))
    )
    (net (code "36") (name "Net-(IC5B-OUT)") (class "Default")
      (node (ref "IC5") (pin "7") (pinfunction "OUT_7") (pintype "output"))
      (node (ref "LED7") (pin "A") (pinfunction "A_A") (pintype "passive"))
    )
    (net (code "37") (name "Net-(IC5C--IN)") (class "Default")
      (node (ref "IC5") (pin "9") (pinfunction "-IN_9") (pintype "input"))
      (node (ref "R13") (pin "1") (pinfunction "1_1") (pintype "passive"))
      (node (ref "R14") (pin "2") (pinfunction "2_2") (pintype "passive"))
    )
    (net (code "38") (name "Net-(IC5C-OUT)") (class "Default")
      (node (ref "IC5") (pin "8") (pinfunction "OUT_8") (pintype "output"))
      (node (ref "LED8") (pin "A") (pinfunction "A_A") (pintype "passive"))
    )
    (net (code "39") (name "Net-(IC5D--IN)") (class "Default")
      (node (ref "IC5") (pin "13") (pinfunction "-IN_13") (pintype "input"))
      (node (ref "R14") (pin "1") (pinfunction "1_1") (pintype "passive"))
      (node (ref "R15") (pin "2") (pinfunction "2_2") (pintype "passive"))
    )
    (net (code "40") (name "Net-(IC5D-OUT)") (class "Default")
      (node (ref "IC5") (pin "14") (pinfunction "OUT_14") (pintype "output"))
      (node (ref "LED9") (pin "A") (pinfunction "A_A") (pintype "passive"))
    )
    (net (code "41") (name "Net-(LED1-PadA)") (class "Default")
      (node (ref "LED1") (pin "A") (pinfunction "A_A") (pintype "passive"))
      (node (ref "R1") (pin "1") (pinfunction "1_1") (pintype "passive"))
    )
    (net (code "42") (name "Net-(LED2-PadC)") (class "Default")
      (node (ref "LED2") (pin "C") (pinfunction "C_C") (pintype "passive"))
      (node (ref "R23") (pin "1") (pinfunction "1_1") (pintype "passive"))
    )
    (net (code "43") (name "Net-(LED3-PadC)") (class "Default")
      (node (ref "LED3") (pin "C") (pinfunction "C_C") (pintype "passive"))
      (node (ref "R24") (pin "1") (pinfunction "1_1") (pintype "passive"))
    )
    (net (code "44") (name "Net-(LED4-PadC)") (class "Default")
      (node (ref "LED4") (pin "C") (pinfunction "C_C") (pintype "passive"))
      (node (ref "R25") (pin "1") (pinfunction "1_1") (pintype "passive"))
    )
    (net (code "45") (name "Net-(LED5-PadC)") (class "Default")
      (node (ref "LED5") (pin "C") (pinfunction "C_C") (pintype "passive"))
      (node (ref "R26") (pin "1") (pinfunction "1_1") (pintype "passive"))
    )
    (net (code "46") (name "Net-(LED6-PadC)") (class "Default")
      (node (ref "LED6") (pin "C") (pinfunction "C_C") (pintype "passive"))
      (node (ref "R27") (pin "1") (pinfunction "1_1") (pintype "passive"))
    )
    (net (code "47") (name "Net-(LED7-PadC)") (class "Default")
      (node (ref "LED7") (pin "C") (pinfunction "C_C") (pintype "passive"))
      (node (ref "R28") (pin "1") (pinfunction "1_1") (pintype "passive"))
    )
    (net (code "48") (name "Net-(LED8-PadC)") (class "Default")
      (node (ref "LED8") (pin "C") (pinfunction "C_C") (pintype "passive"))
      (node (ref "R29") (pin "1") (pinfunction "1_1") (pintype "passive"))
    )
    (net (code "49") (name "Net-(LED9-PadC)") (class "Default")
      (node (ref "LED9") (pin "C") (pinfunction "C_C") (pintype "passive"))
      (node (ref "R30") (pin "1") (pinfunction "1_1") (pintype "passive"))
    )
    (net (code "50") (name "Net-(Q1-B)") (class "Default")
      (node (ref "Q1") (pin "1") (pinfunction "B_1") (pintype "passive"))
      (node (ref "R16") (pin "2") (pinfunction "2_2") (pintype "passive"))
    )
    (net (code "51") (name "Net-(Q1-C)") (class "Default")
      (node (ref "Q1") (pin "3") (pinfunction "C_3") (pintype "passive"))
      (node (ref "R4") (pin "1") (pinfunction "1_1") (pintype "passive"))
      (node (ref "R5") (pin "2") (pinfunction "2_2") (pintype "passive"))
    )
    (net (code "52") (name "Net-(R2-S)") (class "Default")
      (node (ref "R2") (pin "2") (pinfunction "S_2") (pintype "passive"))
      (node (ref "S3") (pin "3") (pinfunction "3_3") (pintype "bidirectional"))
    )
    (net (code "53") (name "Net-(R6-Pad1)") (class "Default")
      (node (ref "R6") (pin "1") (pinfunction "1_1") (pintype "passive"))
      (node (ref "R7") (pin "2") (pinfunction "2_2") (pintype "passive"))
    )
    (net (code "54") (name "Net-(S1-Pad2)") (class "Default")
      (node (ref "S1") (pin "2") (pinfunction "2_2") (pintype "bidirectional"))
      (node (ref "S2") (pin "4") (pinfunction "4_4") (pintype "bidirectional"))
    )
    (net (code "55") (name "Net-(S1-Pad5)") (class "Default")
      (node (ref "S1") (pin "5") (pinfunction "5_5") (pintype "bidirectional"))
      (node (ref "S2") (pin "6") (pinfunction "6_6") (pintype "bidirectional"))
    )
    (net (code "56") (name "Net-(U$1-VCONTROL)") (class "Default")
      (node (ref "R18") (pin "2") (pinfunction "2_2") (pintype "passive"))
      (node (ref "R19") (pin "2") (pinfunction "2_2") (pintype "passive"))
      (node (ref "U$1") (pin "P$4") (pinfunction "VCONTROL_P$4") (pintype "bidirectional"))
      (node (ref "U$1") (pin "P$5") (pinfunction "VIN_P$5") (pintype "bidirectional"))
    )
    (net (code "57") (name "Net-(U1-ESR)") (class "Default")
      (node (ref "C4") (pin "1") (pinfunction "1_1") (pintype "passive"))
      (node (ref "U1") (pin "4") (pinfunction "ESR_4") (pintype "passive"))
    )
    (net (code "58") (name "Net-(U2-BYPASS)") (class "Default")
      (node (ref "C6") (pin "1") (pinfunction "1_1") (pintype "passive"))
      (node (ref "U2") (pin "4") (pinfunction "BYPASS_4") (pintype "passive"))
    )
    (net (code "59") (name "ON1") (class "Default")
      (node (ref "SW4") (pin "ON1") (pinfunction "ON1_ON1") (pintype "power_in"))
    )
    (net (code "60") (name "VCC") (class "Default")
      (node (ref "C13") (pin "1") (pinfunction "1_1") (pintype "passive"))
      (node (ref "C3") (pin "+") (pinfunction "+_+") (pintype "passive"))
      (node (ref "IC3") (pin "1") (pinfunction "V+_1") (pintype "passive"))
      (node (ref "J2") (pin "P$2") (pinfunction "P$1_P$2") (pintype "bidirectional"))
      (node (ref "J2") (pin "P$4") (pinfunction "P$1_P$4") (pintype "bidirectional"))
      (node (ref "J3") (pin "3") (pinfunction "3_3") (pintype "passive"))
      (node (ref "J9") (pin "P$1") (pinfunction "P$1_P$1") (pintype "bidirectional"))
      (node (ref "JP2") (pin "1") (pinfunction "1_1") (pintype "passive"))
      (node (ref "JP2") (pin "2") (pinfunction "2_2") (pintype "passive"))
      (node (ref "S1") (pin "3") (pinfunction "3_3") (pintype "bidirectional"))
      (node (ref "TEST_PADS") (pin "3") (pinfunction "3_3") (pintype "bidirectional"))
      (node (ref "TP_VCC") (pin "TP") (pinfunction "TP_TP") (pintype "input"))
      (node (ref "U$1") (pin "P$3") (pinfunction "VOUT_P$3") (pintype "bidirectional"))
    )
    (net (code "61") (name "VIN") (class "Default")
      (node (ref "C1") (pin "+") (pinfunction "+_+") (pintype "passive"))
      (node (ref "C14") (pin "1") (pinfunction "1_1") (pintype "passive"))
      (node (ref "D1") (pin "A") (pinfunction "A_A") (pintype "passive"))
      (node (ref "F3") (pin "1") (pinfunction "P$1_1") (pintype "bidirectional"))
      (node (ref "IC2") (pin "4") (pinfunction "V+_4") (pintype "power_in"))
      (node (ref "IC4") (pin "4") (pinfunction "V+_4") (pintype "power_in"))
      (node (ref "IC5") (pin "4") (pinfunction "V+_4") (pintype "power_in"))
      (node (ref "J3") (pin "6") (pinfunction "6_6") (pintype "passive"))
      (node (ref "J7") (pin "P$1") (pinfunction "P$1_P$1") (pintype "bidirectional"))
      (node (ref "PS1") (pin "1") (pinfunction "+VIN_1") (pintype "input"))
      (node (ref "R1") (pin "2") (pinfunction "2_2") (pintype "passive"))
      (node (ref "R19") (pin "1") (pinfunction "1_1") (pintype "passive"))
      (node (ref "R20") (pin "2") (pinfunction "2_2") (pintype "passive"))
      (node (ref "SW4") (pin "ON2") (pinfunction "ON2_ON2") (pintype "power_in"))
      (node (ref "U1") (pin "1") (pinfunction "VIN_1") (pintype "input"))
      (node (ref "U1") (pin "3") (pinfunction "ON/~{OFF}_3") (pintype "passive"))
      (node (ref "U2") (pin "1") (pinfunction "VIN_1") (pintype "input"))
      (node (ref "U2") (pin "3") (pinfunction "ON/~{OFF}_3") (pintype "passive"))
    )
    (net (code "62") (name "VOLT_RANGE") (class "Default")
      (node (ref "R6") (pin "2") (pinfunction "2_2") (pintype "passive"))
      (node (ref "S2") (pin "2") (pinfunction "2_2") (pintype "bidirectional"))
    )
    (net (code "63") (name "V_SET") (class "Default")
      (node (ref "IC2") (pin "3") (pinfunction "+IN_3") (pintype "input"))
      (node (ref "S1") (pin "1") (pinfunction "1_1") (pintype "bidirectional"))
      (node (ref "S3") (pin "2") (pinfunction "2_2") (pintype "bidirectional"))
      (node (ref "TEST_PADS") (pin "4") (pinfunction "4_4") (pintype "bidirectional"))
      (node (ref "TP_VSET") (pin "TP") (pinfunction "TP_TP") (pintype "input"))
    )
    (net (code "64") (name "V_SET_MICRO") (class "Default")
      (node (ref "J3") (pin "5") (pinfunction "5_5") (pintype "passive"))
      (node (ref "S3") (pin "1") (pinfunction "1_1") (pintype "bidirectional"))
    )
    (net (code "65") (name "unconnected-(KK1-K-PadK1)") (class "Default")
      (node (ref "KK1") (pin "K1") (pinfunction "K_K1") (pintype "passive"))
    )
    (net (code "66") (name "unconnected-(KK1-K-PadK2)") (class "Default")
      (node (ref "KK1") (pin "K2") (pinfunction "K_K2") (pintype "passive"))
    )
    (net (code "67") (name "unconnected-(U$2-PadP$1)") (class "Default")
      (node (ref "U$2") (pin "P$1") (pinfunction "P$1_P$1") (pintype "bidirectional"))
    )
    (net (code "68") (name "unconnected-(U$3-PadP$1)") (class "Default")
      (node (ref "U$3") (pin "P$1") (pinfunction "P$1_P$1") (pintype "bidirectional"))
    )
  )
)
